# design.net
KiCad netlist of a schematic drawn in Altium Designer
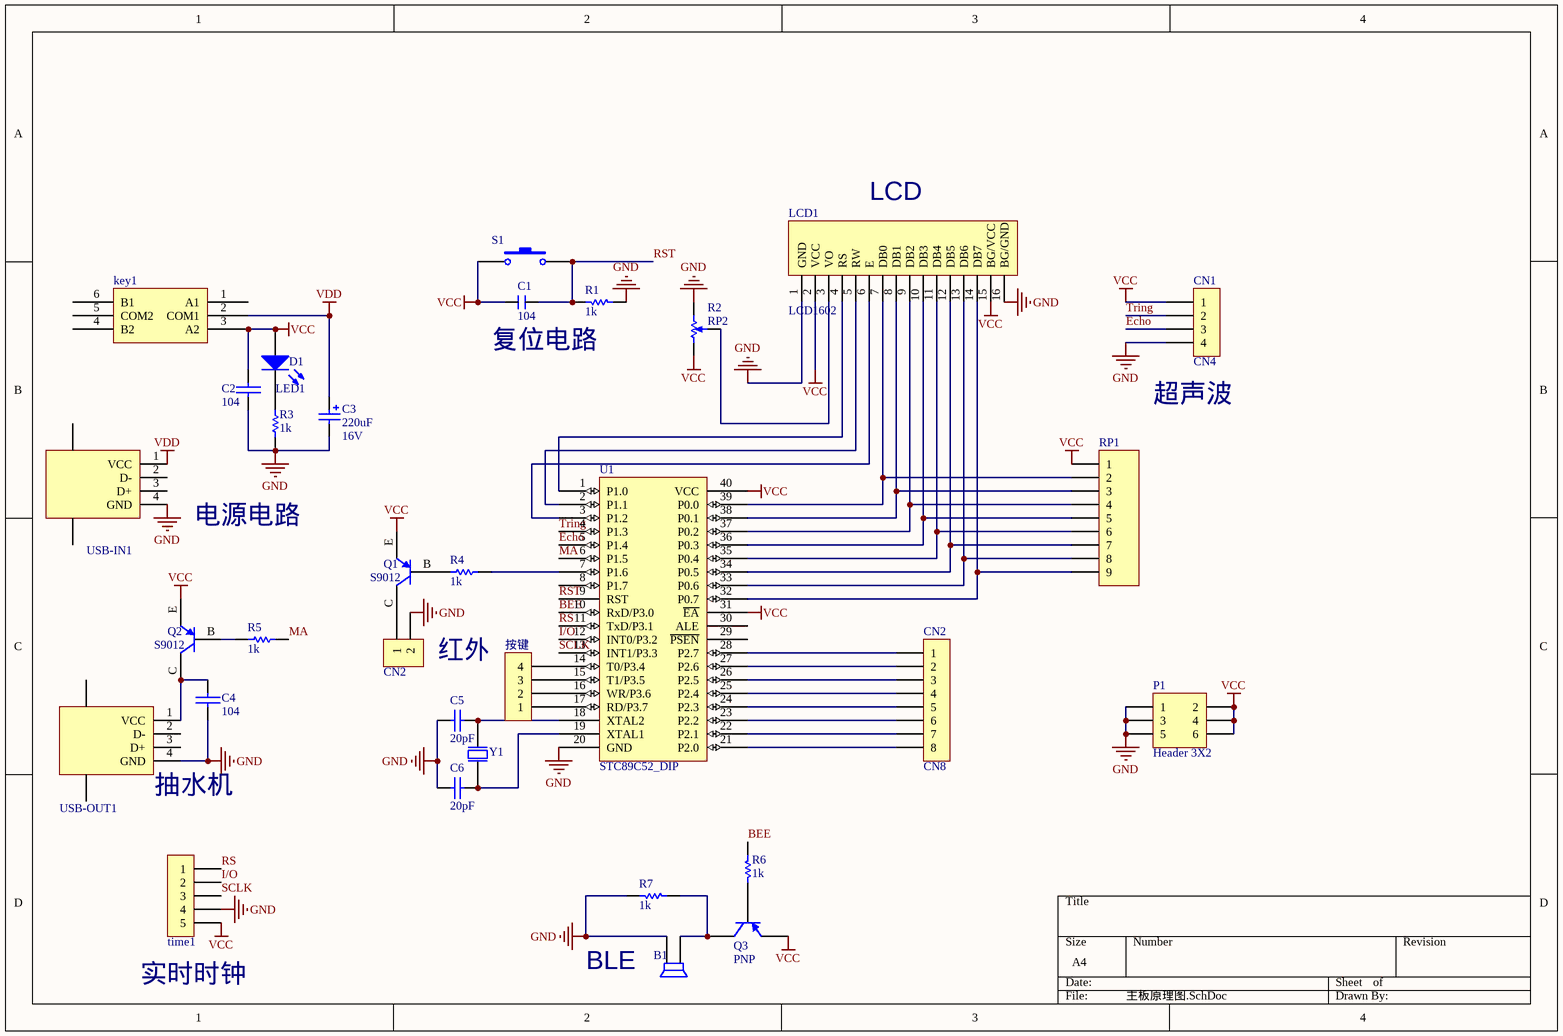
[diagram p0: 主板原理图.SchDoc]

(export (version "E")
  (design (tool "Eeschema 10.0.6"))
  (components
    (comp (ref "B1") (value "BUZZ") (footprint "BUZZER") (libsource (lib "6开关蜂鸣器电池等") (part "BUZZ")))
    (comp (ref "C1")
      (value "CAP")
      (footprint "RAD-0.1")
      (description "无极性")
      (fields (field (name "ALTIUM_UNNAMED_1") "104"))
      (libsource (lib "1阻容电感元件") (part "CAP"))
    )
    (comp (ref "C2")
      (value "104")
      (footprint "RAD-0.1")
      (description "电容")
      (libsource (lib "C8051F020最小2") (part "CAP"))
    )
    (comp (ref "C3")
      (value "220uF")
      (footprint "CAPPR2.5-6.3X11.5")
      (description "Polarized Capacitor (Radial)")
      (fields
        (field (name "VOLTAGE") "16V")
        (field (name "Comment") "Cap Pol")
        (field (name "PUBLISHER") "Altium Limited")
      )
      (libsource (lib "03-EButterflyIntegratedLibrary") (part "Cap Pol"))
    )
    (comp (ref "C4")
      (value "104")
      (footprint "RAD-0.1")
      (description "电容")
      (libsource (lib "C8051F020最小2") (part "CAP"))
    )
    (comp (ref "C5")
      (value "20pF")
      (footprint "RAD-0.1")
      (description "Capacitor")
      (fields (field (name "Comment") "Cap") (field (name "PUBLISHER") "Altium Limited"))
      (libsource (lib "Miscellaneous Devices") (part "Cap"))
    )
    (comp (ref "C6")
      (value "20pF")
      (footprint "RAD-0.1")
      (description "Capacitor")
      (fields (field (name "Comment") "Cap") (field (name "PUBLISHER") "Altium Limited"))
      (libsource (lib "Miscellaneous Devices") (part "Cap"))
    )
    (comp (ref "CN1") (value "CN4") (footprint "CN4") (libsource (lib "Schlib1") (part "CN4")))
    (comp (ref "CN2") (value "CN8") (footprint "CN8") (libsource (lib "Schlib1") (part "CN8")))
    (comp (ref "CN3") (value "CN2") (footprint "CN2") (libsource (lib "Schlib1") (part "CN2")))
    (comp (ref "D1")
      (value "LED1")
      (footprint "LED1")
      (description "3mm")
      (libsource (lib "2二极管三极管") (part "LED1"))
    )
    (comp (ref "key1") (value "SW-KEY") (footprint "SW1-key") (libsource (lib "Schlib1") (part "SW-KEY")))
    (comp (ref "LCD1") (value "LCD1602") (footprint "HDR1X16") (libsource (lib "实用原理图库") (part "LCD1602")))
    (comp (ref "P1")
      (value "Header 3X2")
      (footprint "HDR2X3")
      (description "Header, 3-Pin, Dual row")
      (fields (field (name "PUBLISHER") "Altium Limited"))
      (libsource (lib "Connect") (part "Header 3X2"))
    )
    (comp (ref "Q1")
      (value "S9012")
      (footprint "2二极管三极管:TO-92A")
      (description "PNP 三极管")
      (fields (field (name "PUBLISHER") "Altium Limited"))
      (libsource (lib "51单片机原理图库 - 简名") (part "S9012"))
    )
    (comp (ref "Q2")
      (value "S9012")
      (footprint "2二极管三极管:TO-92A")
      (description "PNP 三极管")
      (fields (field (name "PUBLISHER") "Altium Limited"))
      (libsource (lib "51单片机原理图库 - 简名") (part "S9012"))
    )
    (comp (ref "Q3")
      (value "PNP")
      (footprint "TO-92A")
      (description "8550 9012")
      (libsource (lib "2二极管三极管") (part "PNP"))
    )
    (comp (ref "R1")
      (value "1k")
      (footprint "AXIAL-0.5")
      (description "Resistor")
      (fields (field (name "Comment") "Res1") (field (name "PUBLISHER") "Altium Limited"))
      (libsource (lib "Miscellaneous Devices") (part "Res1"))
    )
    (comp (ref "R2")
      (value "RP2")
      (footprint "POT SMALL")
      (description "Square Trimming Potentiometer")
      (fields (field (name "PUBLISHER") "Altium Limited"))
      (libsource (lib "Miscellaneous Devices") (part "RPot SM"))
    )
    (comp (ref "R3")
      (value "1k")
      (footprint "AXIAL-0.5")
      (description "Resistor")
      (fields (field (name "Comment") "Res1") (field (name "PUBLISHER") "Altium Limited"))
      (libsource (lib "Miscellaneous Devices") (part "Res1"))
    )
    (comp (ref "R4")
      (value "1k")
      (footprint "AXIAL-0.5")
      (description "Resistor")
      (fields (field (name "Comment") "Res1") (field (name "PUBLISHER") "Altium Limited"))
      (libsource (lib "Miscellaneous Devices") (part "Res1"))
    )
    (comp (ref "R5")
      (value "1k")
      (footprint "AXIAL-0.5")
      (description "Resistor")
      (fields (field (name "Comment") "Res1") (field (name "PUBLISHER") "Altium Limited"))
      (libsource (lib "Miscellaneous Devices") (part "Res1"))
    )
    (comp (ref "R6")
      (value "1k")
      (footprint "AXIAL-0.5")
      (description "Resistor")
      (fields (field (name "Comment") "Res1") (field (name "PUBLISHER") "Altium Limited"))
      (libsource (lib "Miscellaneous Devices") (part "Res1"))
    )
    (comp (ref "R7")
      (value "1k")
      (footprint "AXIAL-0.5")
      (description "Resistor")
      (fields (field (name "Comment") "Res1") (field (name "PUBLISHER") "Altium Limited"))
      (libsource (lib "Miscellaneous Devices") (part "Res1"))
    )
    (comp (ref "RP1")
      (value "Header 9")
      (footprint "HDR1X9")
      (description "Header, 9-Pin")
      (fields (field (name "PUBLISHER") "Altium Limited"))
      (libsource (lib "3接插件") (part "Header 9"))
    )
    (comp (ref "S1")
      (value "SW-PB")
      (footprint "SW-TH_4PIN-L6.00-W6.00")
      (description "Switch")
      (fields (field (name "PUBLISHER") "Altium Limited"))
      (libsource (lib "Miscellaneous Devices") (part "SW-PB"))
    )
    (comp (ref "time1") (value "CN5") (footprint "CN5") (libsource (lib "Schlib1") (part "CN5")))
    (comp (ref "U1")
      (value "STC89C52_DIP")
      (footprint "DIP-40")
      (libsource (lib "02 Miscellaneous_Devices_ZSF_Library") (part "STC89C52_DIP"))
    )
    (comp (ref "USB-IN1")
      (value "USB-O")
      (footprint "USB-B-TH_4PIN-H-FEMALE-PITCH2.50-TR_U241-041N-1WR85-5")
      (libsource (lib "Schlib1") (part "USB-O"))
    )
    (comp (ref "USB-OUT1") (value "USB-O") (footprint "USB-O") (libsource (lib "Schlib1") (part "USB-O")))
    (comp (ref "Y1")
      (value "XTAL")
      (footprint "XTAL-49/U_N")
      (description "Crystal Oscillator")
      (fields (field (name "PUBLISHER") "Altium Limited"))
      (libsource (lib "03-EButterflyIntegratedLibrary") (part "XTAL"))
    )
    (comp (ref "按键") (value "CN4") (footprint "CN4") (libsource (lib "") (part "CN4_1")))
  )
  (nets
    (net (code "1") (name "/BEE") (class "Default")
      (node (ref "R6") (pin "1") (pinfunction "1_1") (pintype "passive"))
      (node (ref "U1") (pin "10") (pinfunction "RxD/P3.0_10") (pintype "bidirectional"))
    )
    (net (code "2") (name "/Echo") (class "Default")
      (node (ref "CN1") (pin "3") (pinfunction "3_3") (pintype "passive"))
      (node (ref "U1") (pin "5") (pinfunction "P1.4_5") (pintype "bidirectional"))
    )
    (net (code "3") (name "/I{slash}O") (class "Default")
      (node (ref "U1") (pin "12") (pinfunction "INT0/P3.2_12") (pintype "bidirectional"))
      (node (ref "time1") (pin "2") (pinfunction "2_2") (pintype "passive"))
    )
    (net (code "4") (name "/MA") (class "Default")
      (node (ref "R5") (pin "2") (pinfunction "2_2") (pintype "passive"))
      (node (ref "U1") (pin "6") (pinfunction "P1.5_6") (pintype "bidirectional"))
    )
    (net (code "5") (name "/RS") (class "Default")
      (node (ref "U1") (pin "11") (pinfunction "TxD/P3.1_11") (pintype "bidirectional"))
      (node (ref "time1") (pin "1") (pinfunction "1_1") (pintype "passive"))
    )
    (net (code "6") (name "/RST") (class "Default")
      (node (ref "C1") (pin "2") (pinfunction "2_2") (pintype "passive"))
      (node (ref "R1") (pin "2") (pinfunction "2_2") (pintype "passive"))
      (node (ref "S1") (pin "1") (pinfunction "1_1") (pintype "passive"))
      (node (ref "U1") (pin "9") (pinfunction "RST_9") (pintype "passive"))
    )
    (net (code "7") (name "/SCLK") (class "Default")
      (node (ref "U1") (pin "13") (pinfunction "INT1/P3.3_13") (pintype "bidirectional"))
      (node (ref "time1") (pin "3") (pinfunction "3_3") (pintype "passive"))
    )
    (net (code "8") (name "/Tring") (class "Default")
      (node (ref "CN1") (pin "2") (pinfunction "2_2") (pintype "passive"))
      (node (ref "U1") (pin "4") (pinfunction "P1.3_4") (pintype "bidirectional"))
    )
    (net (code "9") (name "GND") (class "Default")
      (node (ref "B1") (pin "1") (pinfunction "1_1") (pintype "passive"))
      (node (ref "C2") (pin "1") (pinfunction "1_1") (pintype "passive"))
      (node (ref "C3") (pin "2") (pinfunction "2_2") (pintype "passive"))
      (node (ref "C4") (pin "1") (pinfunction "1_1") (pintype "passive"))
      (node (ref "C5") (pin "1") (pinfunction "1_1") (pintype "passive"))
      (node (ref "C6") (pin "2") (pinfunction "2_2") (pintype "passive"))
      (node (ref "CN1") (pin "4") (pinfunction "4_4") (pintype "passive"))
      (node (ref "CN3") (pin "2") (pinfunction "2_2") (pintype "passive"))
      (node (ref "LCD1") (pin "1") (pinfunction "GND_1") (pintype "passive"))
      (node (ref "LCD1") (pin "16") (pinfunction "BG/GND_16") (pintype "passive"))
      (node (ref "P1") (pin "1") (pinfunction "1_1") (pintype "passive"))
      (node (ref "P1") (pin "3") (pinfunction "3_3") (pintype "passive"))
      (node (ref "P1") (pin "5") (pinfunction "5_5") (pintype "passive"))
      (node (ref "R1") (pin "1") (pinfunction "1_1") (pintype "passive"))
      (node (ref "R2") (pin "CW") (pinfunction "+_CW") (pintype "passive"))
      (node (ref "R3") (pin "1") (pinfunction "1_1") (pintype "passive"))
      (node (ref "R7") (pin "2") (pinfunction "2_2") (pintype "passive"))
      (node (ref "U1") (pin "20") (pinfunction "GND_20") (pintype "power_in"))
      (node (ref "USB-IN1") (pin "4") (pinfunction "GND_4") (pintype "passive"))
      (node (ref "USB-OUT1") (pin "4") (pinfunction "GND_4") (pintype "passive"))
      (node (ref "time1") (pin "4") (pinfunction "4_4") (pintype "passive"))
    )
    (net (code "10") (name "Net-(B1-Pad2)") (class "Default")
      (node (ref "B1") (pin "2") (pinfunction "2_2") (pintype "passive"))
      (node (ref "Q3") (pin "C") (pinfunction "C_C") (pintype "passive"))
      (node (ref "R7") (pin "1") (pinfunction "1_1") (pintype "passive"))
    )
    (net (code "11") (name "Net-(CN3-Pad1)") (class "Default")
      (node (ref "CN3") (pin "1") (pinfunction "1_1") (pintype "passive"))
      (node (ref "Q1") (pin "C") (pinfunction "C_C") (pintype "passive"))
    )
    (net (code "12") (name "Net-(D1-K)") (class "Default")
      (node (ref "D1") (pin "2") (pinfunction "K_2") (pintype "passive"))
      (node (ref "R3") (pin "2") (pinfunction "2_2") (pintype "passive"))
    )
    (net (code "13") (name "Net-(LCD1-DB0)") (class "Default")
      (node (ref "LCD1") (pin "7") (pinfunction "DB0_7") (pintype "passive"))
      (node (ref "RP1") (pin "2") (pinfunction "2_2") (pintype "passive"))
      (node (ref "U1") (pin "39") (pinfunction "P0.0_39") (pintype "bidirectional"))
    )
    (net (code "14") (name "Net-(LCD1-DB1)") (class "Default")
      (node (ref "LCD1") (pin "8") (pinfunction "DB1_8") (pintype "passive"))
      (node (ref "RP1") (pin "3") (pinfunction "3_3") (pintype "passive"))
      (node (ref "U1") (pin "38") (pinfunction "P0.1_38") (pintype "bidirectional"))
    )
    (net (code "15") (name "Net-(LCD1-DB2)") (class "Default")
      (node (ref "LCD1") (pin "9") (pinfunction "DB2_9") (pintype "passive"))
      (node (ref "RP1") (pin "4") (pinfunction "4_4") (pintype "passive"))
      (node (ref "U1") (pin "37") (pinfunction "P0.2_37") (pintype "bidirectional"))
    )
    (net (code "16") (name "Net-(LCD1-DB3)") (class "Default")
      (node (ref "LCD1") (pin "10") (pinfunction "DB3_10") (pintype "passive"))
      (node (ref "RP1") (pin "5") (pinfunction "5_5") (pintype "passive"))
      (node (ref "U1") (pin "36") (pinfunction "P0.3_36") (pintype "bidirectional"))
    )
    (net (code "17") (name "Net-(LCD1-DB4)") (class "Default")
      (node (ref "LCD1") (pin "11") (pinfunction "DB4_11") (pintype "passive"))
      (node (ref "RP1") (pin "6") (pinfunction "6_6") (pintype "passive"))
      (node (ref "U1") (pin "35") (pinfunction "P0.4_35") (pintype "bidirectional"))
    )
    (net (code "18") (name "Net-(LCD1-DB5)") (class "Default")
      (node (ref "LCD1") (pin "12") (pinfunction "DB5_12") (pintype "passive"))
      (node (ref "RP1") (pin "7") (pinfunction "7_7") (pintype "passive"))
      (node (ref "U1") (pin "34") (pinfunction "P0.5_34") (pintype "bidirectional"))
    )
    (net (code "19") (name "Net-(LCD1-DB6)") (class "Default")
      (node (ref "LCD1") (pin "13") (pinfunction "DB6_13") (pintype "passive"))
      (node (ref "RP1") (pin "8") (pinfunction "8_8") (pintype "passive"))
      (node (ref "U1") (pin "33") (pinfunction "P0.6_33") (pintype "bidirectional"))
    )
    (net (code "20") (name "Net-(LCD1-DB7)") (class "Default")
      (node (ref "LCD1") (pin "14") (pinfunction "DB7_14") (pintype "passive"))
      (node (ref "RP1") (pin "9") (pinfunction "9_9") (pintype "passive"))
      (node (ref "U1") (pin "32") (pinfunction "P0.7_32") (pintype "bidirectional"))
    )
    (net (code "21") (name "Net-(LCD1-E)") (class "Default")
      (node (ref "LCD1") (pin "6") (pinfunction "E_6") (pintype "passive"))
      (node (ref "U1") (pin "3") (pinfunction "P1.2_3") (pintype "bidirectional"))
    )
    (net (code "22") (name "Net-(LCD1-RS)") (class "Default")
      (node (ref "LCD1") (pin "4") (pinfunction "RS_4") (pintype "passive"))
      (node (ref "U1") (pin "1") (pinfunction "P1.0_1") (pintype "bidirectional"))
    )
    (net (code "23") (name "Net-(LCD1-RW)") (class "Default")
      (node (ref "LCD1") (pin "5") (pinfunction "RW_5") (pintype "passive"))
      (node (ref "U1") (pin "2") (pinfunction "P1.1_2") (pintype "bidirectional"))
    )
    (net (code "24") (name "Net-(LCD1-VO)") (class "Default")
      (node (ref "LCD1") (pin "3") (pinfunction "VO_3") (pintype "passive"))
      (node (ref "R2") (pin "W") (pinfunction "W_W") (pintype "passive"))
    )
    (net (code "25") (name "Net-(Q1-PadB)") (class "Default")
      (node (ref "Q1") (pin "B") (pinfunction "B_B") (pintype "passive"))
      (node (ref "R4") (pin "1") (pinfunction "1_1") (pintype "passive"))
    )
    (net (code "26") (name "Net-(Q2-PadB)") (class "Default")
      (node (ref "Q2") (pin "B") (pinfunction "B_B") (pintype "passive"))
      (node (ref "R5") (pin "1") (pinfunction "1_1") (pintype "passive"))
    )
    (net (code "27") (name "Net-(Q3-PadB)") (class "Default")
      (node (ref "Q3") (pin "B") (pinfunction "B_B") (pintype "passive"))
      (node (ref "R6") (pin "2") (pinfunction "2_2") (pintype "passive"))
    )
    (net (code "28") (name "Net-(U1-P1.6)") (class "Default")
      (node (ref "R4") (pin "2") (pinfunction "2_2") (pintype "passive"))
      (node (ref "U1") (pin "7") (pinfunction "P1.6_7") (pintype "bidirectional"))
    )
    (net (code "29") (name "Net-(U1-P2.0)") (class "Default")
      (node (ref "CN2") (pin "8") (pinfunction "8_8") (pintype "passive"))
      (node (ref "U1") (pin "21") (pinfunction "P2.0_21") (pintype "bidirectional"))
    )
    (net (code "30") (name "Net-(U1-P2.1)") (class "Default")
      (node (ref "CN2") (pin "7") (pinfunction "7_7") (pintype "passive"))
      (node (ref "U1") (pin "22") (pinfunction "P2.1_22") (pintype "bidirectional"))
    )
    (net (code "31") (name "Net-(U1-P2.2)") (class "Default")
      (node (ref "CN2") (pin "6") (pinfunction "6_6") (pintype "passive"))
      (node (ref "U1") (pin "23") (pinfunction "P2.2_23") (pintype "bidirectional"))
    )
    (net (code "32") (name "Net-(U1-P2.3)") (class "Default")
      (node (ref "CN2") (pin "5") (pinfunction "5_5") (pintype "passive"))
      (node (ref "U1") (pin "24") (pinfunction "P2.3_24") (pintype "bidirectional"))
    )
    (net (code "33") (name "Net-(U1-P2.4)") (class "Default")
      (node (ref "CN2") (pin "4") (pinfunction "4_4") (pintype "passive"))
      (node (ref "U1") (pin "25") (pinfunction "P2.4_25") (pintype "bidirectional"))
    )
    (net (code "34") (name "Net-(U1-P2.5)") (class "Default")
      (node (ref "CN2") (pin "3") (pinfunction "3_3") (pintype "passive"))
      (node (ref "U1") (pin "26") (pinfunction "P2.5_26") (pintype "bidirectional"))
    )
    (net (code "35") (name "Net-(U1-P2.6)") (class "Default")
      (node (ref "CN2") (pin "2") (pinfunction "2_2") (pintype "passive"))
      (node (ref "U1") (pin "27") (pinfunction "P2.6_27") (pintype "bidirectional"))
    )
    (net (code "36") (name "Net-(U1-P2.7)") (class "Default")
      (node (ref "CN2") (pin "1") (pinfunction "1_1") (pintype "passive"))
      (node (ref "U1") (pin "28") (pinfunction "P2.7_28") (pintype "bidirectional"))
    )
    (net (code "37") (name "Net-(U1-RD{slash}P3.7)") (class "Default")
      (node (ref "U1") (pin "17") (pinfunction "RD/P3.7_17") (pintype "bidirectional"))
      (node (ref "按键") (pin "1") (pinfunction "1_1") (pintype "passive"))
    )
    (net (code "38") (name "Net-(U1-T0{slash}P3.4)") (class "Default")
      (node (ref "U1") (pin "14") (pinfunction "T0/P3.4_14") (pintype "bidirectional"))
      (node (ref "按键") (pin "4") (pinfunction "4_4") (pintype "passive"))
    )
    (net (code "39") (name "Net-(U1-T1{slash}P3.5)") (class "Default")
      (node (ref "U1") (pin "15") (pinfunction "T1/P3.5_15") (pintype "bidirectional"))
      (node (ref "按键") (pin "3") (pinfunction "3_3") (pintype "passive"))
    )
    (net (code "40") (name "Net-(U1-WR{slash}P3.6)") (class "Default")
      (node (ref "U1") (pin "16") (pinfunction "WR/P3.6_16") (pintype "bidirectional"))
      (node (ref "按键") (pin "2") (pinfunction "2_2") (pintype "passive"))
    )
    (net (code "41") (name "Net-(U1-XTAL1)") (class "Default")
      (node (ref "C6") (pin "1") (pinfunction "1_1") (pintype "passive"))
      (node (ref "U1") (pin "19") (pinfunction "XTAL1_19") (pintype "passive"))
      (node (ref "Y1") (pin "1") (pinfunction "OSC1_1") (pintype "passive"))
    )
    (net (code "42") (name "Net-(U1-XTAL2)") (class "Default")
      (node (ref "C5") (pin "2") (pinfunction "2_2") (pintype "passive"))
      (node (ref "U1") (pin "18") (pinfunction "XTAL2_18") (pintype "passive"))
      (node (ref "Y1") (pin "2") (pinfunction "OSC2_2") (pintype "passive"))
    )
    (net (code "43") (name "Net-(USB-OUT1-VCC)") (class "Default")
      (node (ref "C4") (pin "2") (pinfunction "2_2") (pintype "passive"))
      (node (ref "Q2") (pin "C") (pinfunction "C_C") (pintype "passive"))
      (node (ref "USB-OUT1") (pin "1") (pinfunction "VCC_1") (pintype "passive"))
    )
    (net (code "44") (name "VCC") (class "Default")
      (node (ref "C1") (pin "1") (pinfunction "1_1") (pintype "passive"))
      (node (ref "C2") (pin "2") (pinfunction "2_2") (pintype "passive"))
      (node (ref "CN1") (pin "1") (pinfunction "1_1") (pintype "passive"))
      (node (ref "D1") (pin "1") (pinfunction "A_1") (pintype "passive"))
      (node (ref "LCD1") (pin "15") (pinfunction "BG/VCC_15") (pintype "passive"))
      (node (ref "LCD1") (pin "2") (pinfunction "VCC_2") (pintype "passive"))
      (node (ref "P1") (pin "2") (pinfunction "2_2") (pintype "passive"))
      (node (ref "P1") (pin "4") (pinfunction "4_4") (pintype "passive"))
      (node (ref "P1") (pin "6") (pinfunction "6_6") (pintype "passive"))
      (node (ref "Q1") (pin "E") (pinfunction "E_E") (pintype "passive"))
      (node (ref "Q2") (pin "E") (pinfunction "E_E") (pintype "passive"))
      (node (ref "Q3") (pin "E") (pinfunction "E_E") (pintype "passive"))
      (node (ref "R2") (pin "CCW") (pinfunction "-_CCW") (pintype "passive"))
      (node (ref "RP1") (pin "1") (pinfunction "1_1") (pintype "passive"))
      (node (ref "S1") (pin "2") (pinfunction "2_2") (pintype "passive"))
      (node (ref "U1") (pin "31") (pinfunction "~{EA}_31") (pintype "passive"))
      (node (ref "U1") (pin "40") (pinfunction "VCC_40") (pintype "power_in"))
      (node (ref "key1") (pin "3") (pinfunction "A2_3") (pintype "passive"))
      (node (ref "time1") (pin "5") (pinfunction "5_5") (pintype "passive"))
    )
    (net (code "45") (name "VDD") (class "Default")
      (node (ref "C3") (pin "1") (pinfunction "1_1") (pintype "passive"))
      (node (ref "USB-IN1") (pin "1") (pinfunction "VCC_1") (pintype "passive"))
      (node (ref "key1") (pin "2") (pinfunction "COM1_2") (pintype "passive"))
    )
    (net (code "46") (name "unconnected-(U1-ALE-Pad30)") (class "Default")
      (node (ref "U1") (pin "30") (pinfunction "ALE_30") (pintype "passive"))
    )
    (net (code "47") (name "unconnected-(U1-P1.7-Pad8)") (class "Default")
      (node (ref "U1") (pin "8") (pinfunction "P1.7_8") (pintype "bidirectional"))
    )
    (net (code "48") (name "unconnected-(U1-~{PSEN}-Pad29)") (class "Default")
      (node (ref "U1") (pin "29") (pinfunction "~{PSEN}_29") (pintype "passive"))
    )
    (net (code "49") (name "unconnected-(USB-IN1-D+-Pad3)") (class "Default")
      (node (ref "USB-IN1") (pin "3") (pinfunction "D+_3") (pintype "passive"))
    )
    (net (code "50") (name "unconnected-(USB-IN1-D--Pad2)") (class "Default")
      (node (ref "USB-IN1") (pin "2") (pinfunction "D-_2") (pintype "passive"))
    )
    (net (code "51") (name "unconnected-(USB-OUT1-D+-Pad3)") (class "Default")
      (node (ref "USB-OUT1") (pin "3") (pinfunction "D+_3") (pintype "passive"))
    )
    (net (code "52") (name "unconnected-(USB-OUT1-D--Pad2)") (class "Default")
      (node (ref "USB-OUT1") (pin "2") (pinfunction "D-_2") (pintype "passive"))
    )
    (net (code "53") (name "unconnected-(key1-A1-Pad1)") (class "Default")
      (node (ref "key1") (pin "1") (pinfunction "A1_1") (pintype "passive"))
    )
    (net (code "54") (name "unconnected-(key1-B1-Pad6)") (class "Default")
      (node (ref "key1") (pin "6") (pinfunction "B1_6") (pintype "passive"))
    )
    (net (code "55") (name "unconnected-(key1-B2-Pad4)") (class "Default")
      (node (ref "key1") (pin "4") (pinfunction "B2_4") (pintype "passive"))
    )
    (net (code "56") (name "unconnected-(key1-COM2-Pad5)") (class "Default")
      (node (ref "key1") (pin "5") (pinfunction "COM2_5") (pintype "passive"))
    )
  )
)
